# Voltage_Reference_Circuit.net
KiCad netlist of a schematic drawn in Altium Designer
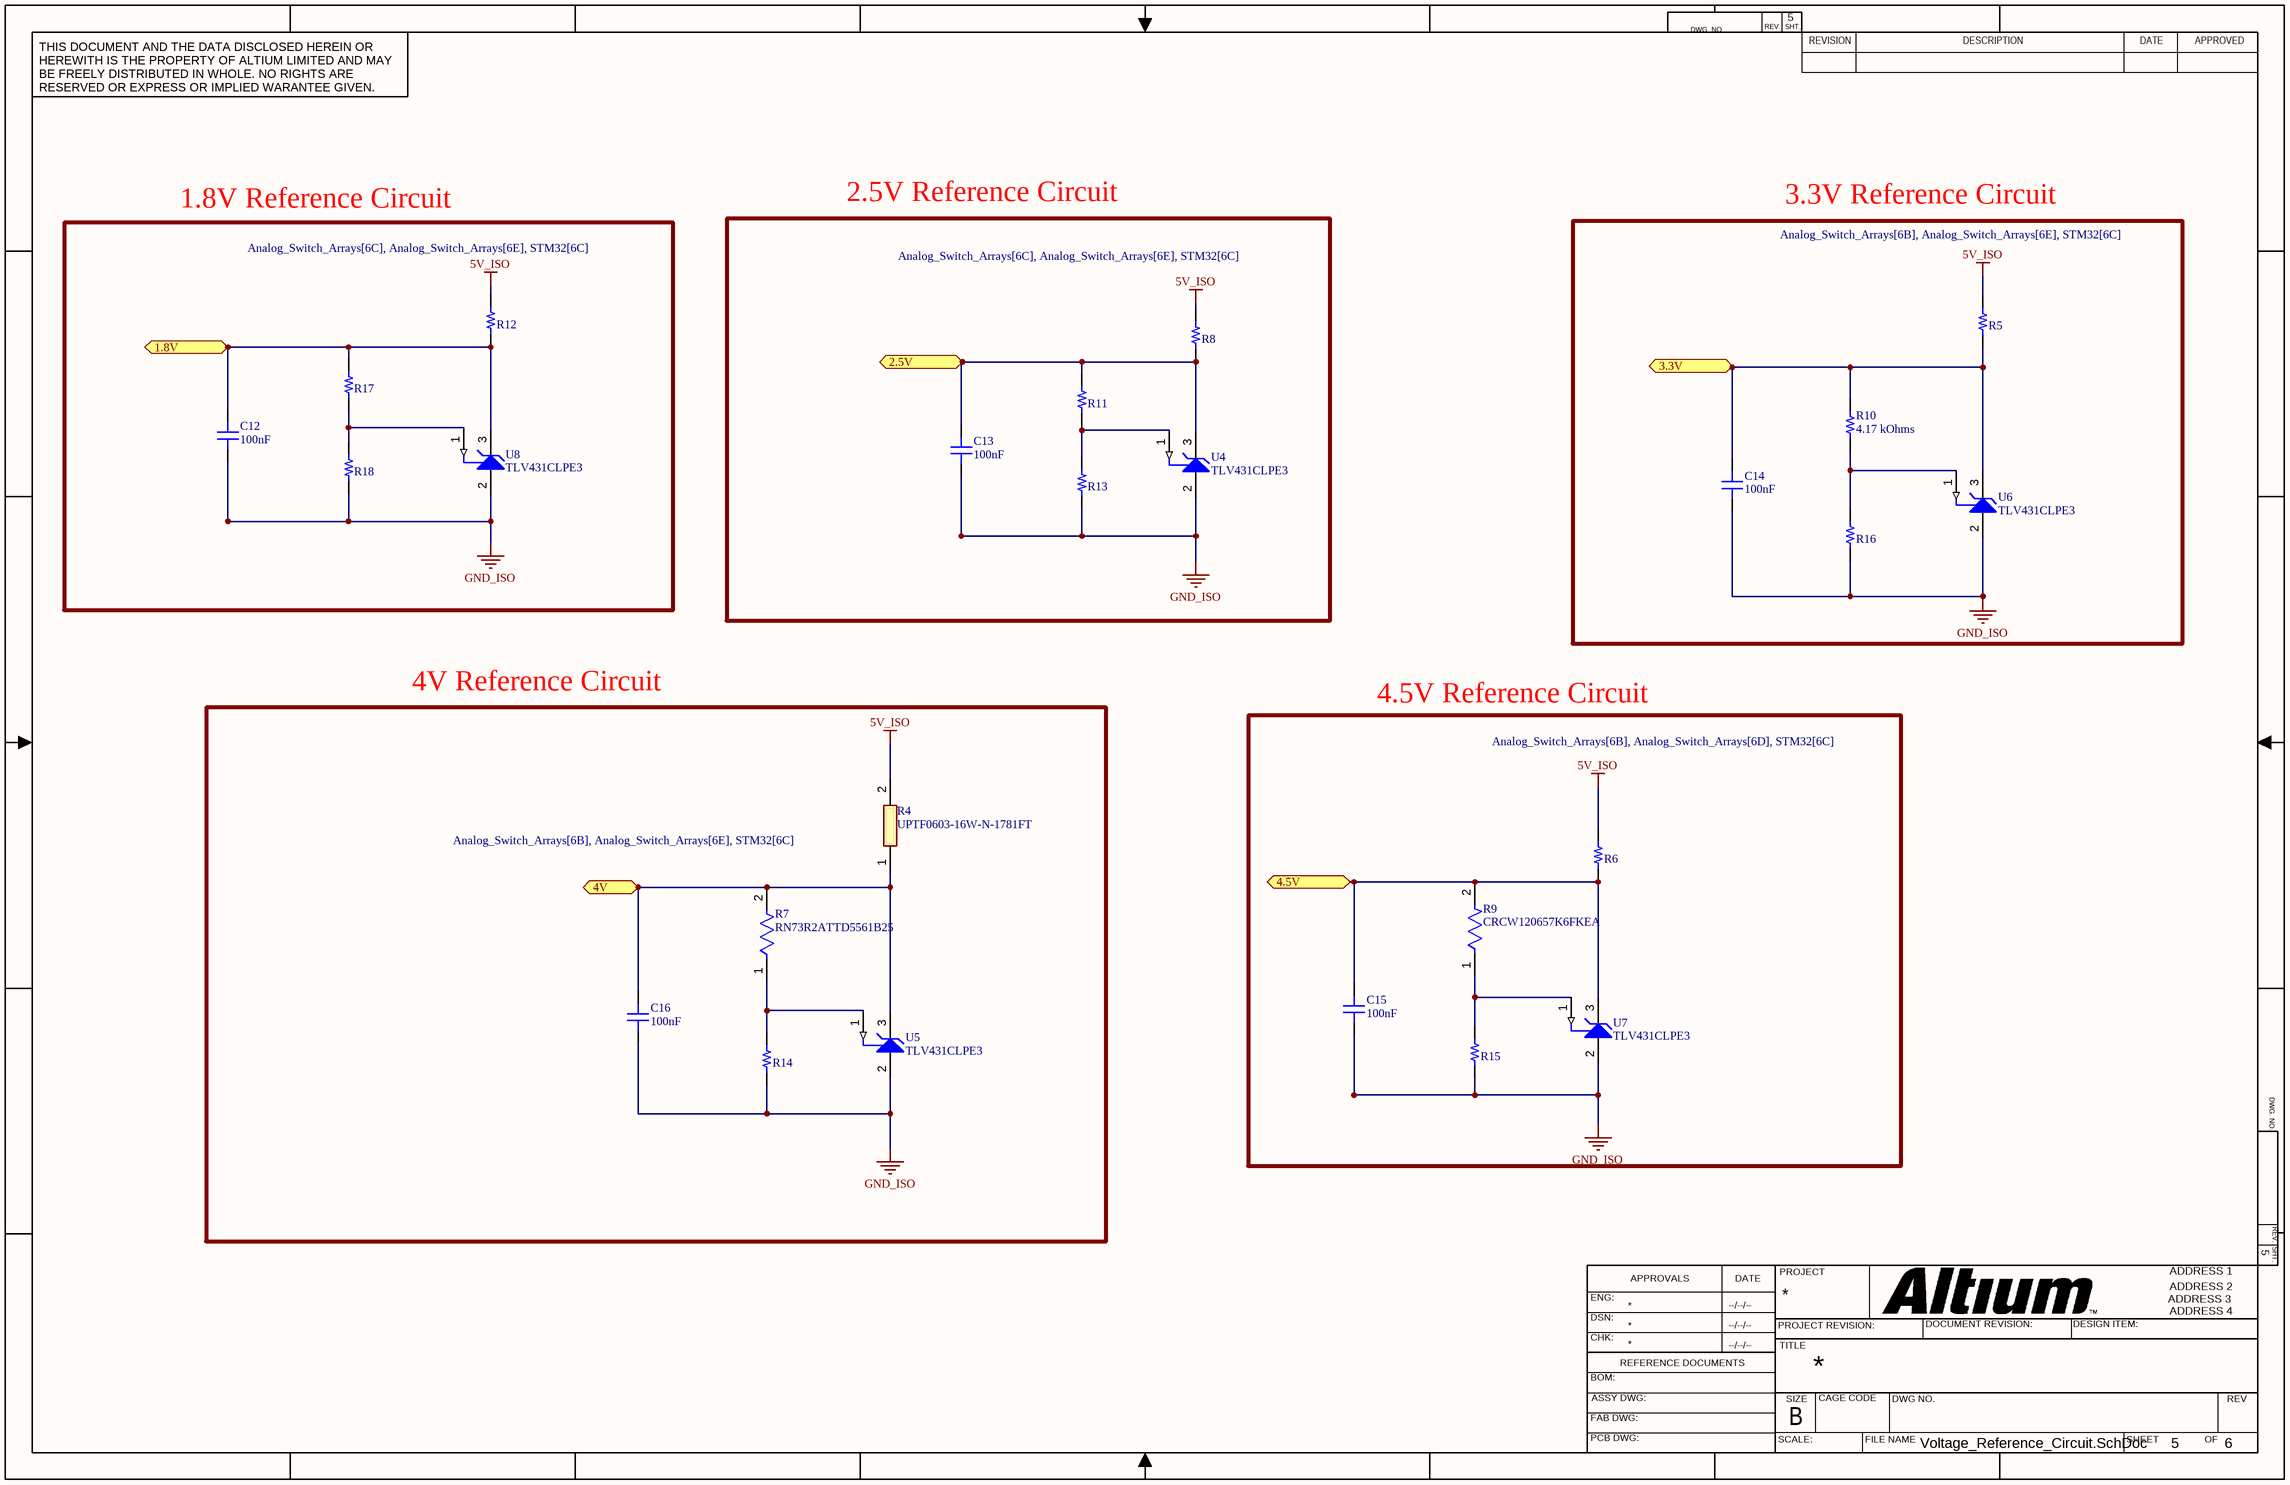
[diagram p0: Voltage_Reference_Circuit.SchDoc]

(export (version "E")
  (design (tool "Eeschema 10.0.6"))
  (components
    (comp (ref "C12")
      (value "100nF")
      (footprint "CAP 1206_3216 - 0.8MM")
      (description "CAP CER 0.1UF 25V X7R 1206")
      (fields (field (name "PART NUMBER") "VJ1206Y104KXXAC"))
      (libsource (lib "University of Massachusetts Lowell") (part "CAPACITOR"))
    )
    (comp (ref "C13")
      (value "100nF")
      (footprint "CAP 1206_3216 - 0.8MM")
      (description "CAP CER 0.1UF 25V X7R 1206")
      (fields (field (name "PART NUMBER") "VJ1206Y104KXXAC"))
      (libsource (lib "University of Massachusetts Lowell") (part "CAPACITOR"))
    )
    (comp (ref "C14")
      (value "100nF")
      (footprint "CAP 1206_3216 - 0.8MM")
      (description "CAP CER 0.1UF 25V X7R 1206")
      (fields (field (name "PART NUMBER") "VJ1206Y104KXXAC"))
      (libsource (lib "University of Massachusetts Lowell") (part "CAPACITOR"))
    )
    (comp (ref "C15")
      (value "100nF")
      (footprint "CAP 1206_3216 - 0.8MM")
      (description "CAP CER 0.1UF 25V X7R 1206")
      (fields (field (name "PART NUMBER") "VJ1206Y104KXXAC"))
      (libsource (lib "University of Massachusetts Lowell") (part "CAPACITOR"))
    )
    (comp (ref "C16")
      (value "100nF")
      (footprint "CAP 1206_3216 - 0.8MM")
      (description "CAP CER 0.1UF 25V X7R 1206")
      (fields (field (name "PART NUMBER") "VJ1206Y104KXXAC"))
      (libsource (lib "University of Massachusetts Lowell") (part "CAPACITOR"))
    )
    (comp (ref "R4")
      (value "UPTF0603-16W-N-1781FT")
      (footprint "SamacSys:RESC1608X55N")
      (description "Resistor")
      (libsource (lib "*") (part "UPTF0603-16W-N-1781FT"))
    )
    (comp (ref "R5")
      (value "RQ73C2B1K69BTD")
      (footprint "RES 1206_3216")
      (description "RES 1.69 KOHMS 0.1% 0.4W 1206")
      (libsource (lib "University of Massachusetts Lowell") (part "RESISTOR"))
    )
    (comp (ref "R6")
      (value "RT1206BRD07442RL")
      (footprint "YAGEO RES 1206_3216")
      (description "RES SMD 442 OHM 0.1% 1/4W 1206")
      (libsource (lib "University of Massachusetts Lowell") (part "RESISTOR"))
    )
    (comp (ref "R7")
      (value "RN73R2ATTD5561B25")
      (footprint "FP-RN73R2A-IPC_C")
      (description "5.56kΩ ±0.1% 0.125W, 1/8W Chip Resistor 0805 (2012 Metric) Moisture Resistant Thin Film")
      (libsource (lib "Altium Content Vault") (part "1029c3af85768c4190bb7ad29bc67b5"))
    )
    (comp (ref "R8")
      (value "KTR18EZPF2491")
      (footprint "RES 1206_3216")
      (description "RES SMD 2.49K OHM 1% 1/4W 1206")
      (libsource (lib "University of Massachusetts Lowell") (part "RESISTOR"))
    )
    (comp (ref "R9")
      (value "CRCW120657K6FKEA")
      (footprint "FP-CRCW1206-e3-IPC_B")
      (description "RES Thick Film, 57.6kΩ, 1%, 0.25W, 100ppm/°C, 1206")
      (fields (field (name "TOLERANCE") "1%"))
      (libsource (lib "Altium Content Vault") (part "1029c3af85768c4190bb7ad29bc67b5"))
    )
    (comp (ref "R10")
      (value "4.17 kOhms")
      (footprint "KOA RES RK73 RN73 0603_1608")
      (description "RES 4.17K OHM 0.1% 1/10W 0603")
      (fields (field (name "PART NUMBER") "RN73R1JTTD4171B25"))
      (libsource (lib "University of Massachusetts Lowell") (part "RESISTOR"))
    )
    (comp (ref "R11")
      (value "RT1206BRD072K55L")
      (footprint "YAGEO RES 1206_3216")
      (description "RES SMD 2.55K OHM 0.1% 1/4W 1206")
      (libsource (lib "University of Massachusetts Lowell") (part "RESISTOR"))
    )
    (comp (ref "R12")
      (value "KTR18EZPF2491")
      (footprint "RES 1206_3216")
      (description "RES SMD 2.49K OHM 1% 1/4W 1206")
      (libsource (lib "University of Massachusetts Lowell") (part "RESISTOR"))
    )
    (comp (ref "R13")
      (value "KTR18EZPF2491")
      (footprint "RES 1206_3216")
      (description "RES SMD 2.49K OHM 1% 1/4W 1206")
      (libsource (lib "University of Massachusetts Lowell") (part "RESISTOR"))
    )
    (comp (ref "R14")
      (value "KTR18EZPF2491")
      (footprint "RES 1206_3216")
      (description "RES SMD 2.49K OHM 1% 1/4W 1206")
      (libsource (lib "University of Massachusetts Lowell") (part "RESISTOR"))
    )
    (comp (ref "R15")
      (value "KTR18EZPF2491")
      (footprint "RES 1206_3216")
      (description "RES SMD 2.49K OHM 1% 1/4W 1206")
      (libsource (lib "University of Massachusetts Lowell") (part "RESISTOR"))
    )
    (comp (ref "R16")
      (value "KTR18EZPF2491")
      (footprint "RES 1206_3216")
      (description "RES SMD 2.49K OHM 1% 1/4W 1206")
      (libsource (lib "University of Massachusetts Lowell") (part "RESISTOR"))
    )
    (comp (ref "R17")
      (value "RK73H2BTTD1131F")
      (footprint "RES 1206_3216")
      (description "RES 1.13K OHM 1% 1/4W 1206")
      (libsource (lib "University of Massachusetts Lowell") (part "RESISTOR"))
    )
    (comp (ref "R18")
      (value "KTR18EZPF2491")
      (footprint "RES 1206_3216")
      (description "RES SMD 2.49K OHM 1% 1/4W 1206")
      (libsource (lib "University of Massachusetts Lowell") (part "RESISTOR"))
    )
    (comp (ref "U4")
      (value "TLV431CLPE3")
      (footprint "TI-LP3")
      (fields (field (name "MANUFACTURER") "Texas Instruments"))
      (libsource (lib "Altium Content Vault") (part "TI-TLV431LP3"))
    )
    (comp (ref "U5")
      (value "TLV431CLPE3")
      (footprint "TI-LP3")
      (fields (field (name "MANUFACTURER") "Texas Instruments"))
      (libsource (lib "Altium Content Vault") (part "TI-TLV431LP3"))
    )
    (comp (ref "U6")
      (value "TLV431CLPE3")
      (footprint "TI-LP3")
      (fields (field (name "MANUFACTURER") "Texas Instruments"))
      (libsource (lib "Altium Content Vault") (part "TI-TLV431LP3"))
    )
    (comp (ref "U7")
      (value "TLV431CLPE3")
      (footprint "TI-LP3")
      (fields (field (name "MANUFACTURER") "Texas Instruments"))
      (libsource (lib "Altium Content Vault") (part "TI-TLV431LP3"))
    )
    (comp (ref "U8")
      (value "TLV431CLPE3")
      (footprint "TI-LP3")
      (fields (field (name "MANUFACTURER") "Texas Instruments"))
      (libsource (lib "Altium Content Vault") (part "TI-TLV431LP3"))
    )
  )
  (nets
    (net (code "1") (name "/1.8V") (class "Default")
      (node (ref "C12") (pin "2") (pinfunction "2_2") (pintype "passive"))
      (node (ref "R12") (pin "1") (pinfunction "1_1") (pintype "passive"))
      (node (ref "R17") (pin "2") (pinfunction "2_2") (pintype "passive"))
      (node (ref "U8") (pin "3") (pinfunction "CATHODE_3") (pintype "passive"))
    )
    (net (code "2") (name "/2.5V") (class "Default")
      (node (ref "C13") (pin "2") (pinfunction "2_2") (pintype "passive"))
      (node (ref "R11") (pin "2") (pinfunction "2_2") (pintype "passive"))
      (node (ref "R8") (pin "1") (pinfunction "1_1") (pintype "passive"))
      (node (ref "U4") (pin "3") (pinfunction "CATHODE_3") (pintype "passive"))
    )
    (net (code "3") (name "/3.3V") (class "Default")
      (node (ref "C14") (pin "2") (pinfunction "2_2") (pintype "passive"))
      (node (ref "R10") (pin "2") (pinfunction "2_2") (pintype "passive"))
      (node (ref "R5") (pin "1") (pinfunction "1_1") (pintype "passive"))
      (node (ref "U6") (pin "3") (pinfunction "CATHODE_3") (pintype "passive"))
    )
    (net (code "4") (name "/4.5V") (class "Default")
      (node (ref "C15") (pin "2") (pinfunction "2_2") (pintype "passive"))
      (node (ref "R6") (pin "1") (pinfunction "1_1") (pintype "passive"))
      (node (ref "R9") (pin "2") (pinfunction "2_2") (pintype "passive"))
      (node (ref "U7") (pin "3") (pinfunction "CATHODE_3") (pintype "passive"))
    )
    (net (code "5") (name "/4V") (class "Default")
      (node (ref "C16") (pin "2") (pinfunction "2_2") (pintype "passive"))
      (node (ref "R4") (pin "1") (pinfunction "1_1") (pintype "passive"))
      (node (ref "R7") (pin "2") (pinfunction "2_2") (pintype "passive"))
      (node (ref "U5") (pin "3") (pinfunction "CATHODE_3") (pintype "passive"))
    )
    (net (code "6") (name "5V_ISO") (class "Default")
      (node (ref "R12") (pin "2") (pinfunction "2_2") (pintype "passive"))
      (node (ref "R4") (pin "2") (pinfunction "2_2") (pintype "passive"))
      (node (ref "R5") (pin "2") (pinfunction "2_2") (pintype "passive"))
      (node (ref "R6") (pin "2") (pinfunction "2_2") (pintype "passive"))
      (node (ref "R8") (pin "2") (pinfunction "2_2") (pintype "passive"))
    )
    (net (code "7") (name "GND_ISO") (class "Default")
      (node (ref "C12") (pin "1") (pinfunction "1_1") (pintype "passive"))
      (node (ref "C13") (pin "1") (pinfunction "1_1") (pintype "passive"))
      (node (ref "C14") (pin "1") (pinfunction "1_1") (pintype "passive"))
      (node (ref "C15") (pin "1") (pinfunction "1_1") (pintype "passive"))
      (node (ref "C16") (pin "1") (pinfunction "1_1") (pintype "passive"))
      (node (ref "R13") (pin "1") (pinfunction "1_1") (pintype "passive"))
      (node (ref "R14") (pin "1") (pinfunction "1_1") (pintype "passive"))
      (node (ref "R15") (pin "1") (pinfunction "1_1") (pintype "passive"))
      (node (ref "R16") (pin "1") (pinfunction "1_1") (pintype "passive"))
      (node (ref "R18") (pin "1") (pinfunction "1_1") (pintype "passive"))
      (node (ref "U4") (pin "2") (pinfunction "ANODE_2") (pintype "passive"))
      (node (ref "U5") (pin "2") (pinfunction "ANODE_2") (pintype "passive"))
      (node (ref "U6") (pin "2") (pinfunction "ANODE_2") (pintype "passive"))
      (node (ref "U7") (pin "2") (pinfunction "ANODE_2") (pintype "passive"))
      (node (ref "U8") (pin "2") (pinfunction "ANODE_2") (pintype "passive"))
    )
    (net (code "8") (name "Net-(U4-REF)") (class "Default")
      (node (ref "R11") (pin "1") (pinfunction "1_1") (pintype "passive"))
      (node (ref "R13") (pin "2") (pinfunction "2_2") (pintype "passive"))
      (node (ref "U4") (pin "1") (pinfunction "REF_1") (pintype "input"))
    )
    (net (code "9") (name "Net-(U5-REF)") (class "Default")
      (node (ref "R14") (pin "2") (pinfunction "2_2") (pintype "passive"))
      (node (ref "R7") (pin "1") (pinfunction "1_1") (pintype "passive"))
      (node (ref "U5") (pin "1") (pinfunction "REF_1") (pintype "input"))
    )
    (net (code "10") (name "Net-(U6-REF)") (class "Default")
      (node (ref "R10") (pin "1") (pinfunction "1_1") (pintype "passive"))
      (node (ref "R16") (pin "2") (pinfunction "2_2") (pintype "passive"))
      (node (ref "U6") (pin "1") (pinfunction "REF_1") (pintype "input"))
    )
    (net (code "11") (name "Net-(U7-REF)") (class "Default")
      (node (ref "R15") (pin "2") (pinfunction "2_2") (pintype "passive"))
      (node (ref "R9") (pin "1") (pinfunction "1_1") (pintype "passive"))
      (node (ref "U7") (pin "1") (pinfunction "REF_1") (pintype "input"))
    )
    (net (code "12") (name "Net-(U8-REF)") (class "Default")
      (node (ref "R17") (pin "1") (pinfunction "1_1") (pintype "passive"))
      (node (ref "R18") (pin "2") (pinfunction "2_2") (pintype "passive"))
      (node (ref "U8") (pin "1") (pinfunction "REF_1") (pintype "input"))
    )
  )
)
